# block_base_M.net
KiCad netlist of a schematic drawn in EAGLE
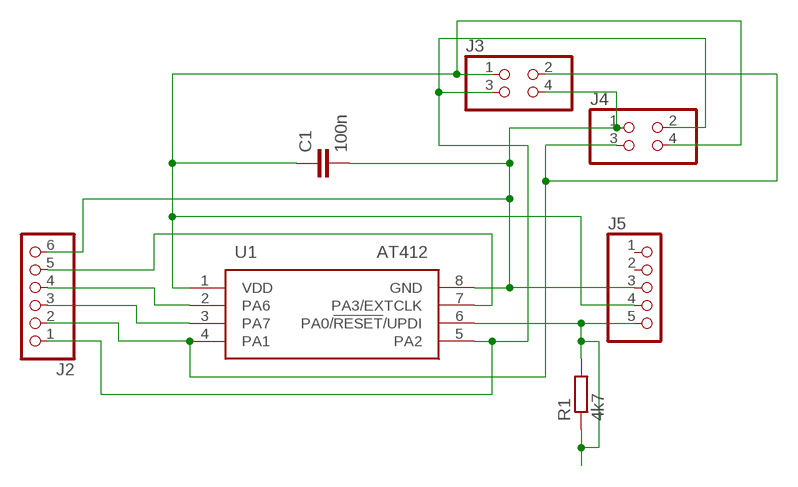
[diagram p0: schematic, sheet 1]

(export (version "E")
  (design (tool "Eeschema 10.0.6"))
  (components
    (comp (ref "C1")
      (value "100n")
      (footprint "eagle-import:C0603")
      (libsource (lib "eagle-import") (part "C-EUC0603"))
    )
    (comp (ref "J2")
      (value "PINHD-1X6")
      (footprint "eagle-import:1X06")
      (libsource (lib "eagle-import") (part "PINHD-1X6"))
    )
    (comp (ref "J3")
      (value "PINHD-2X2")
      (footprint "eagle-import:2X02")
      (libsource (lib "eagle-import") (part "PINHD-2X2"))
    )
    (comp (ref "J4")
      (value "PINHD-2X2")
      (footprint "eagle-import:2X02")
      (libsource (lib "eagle-import") (part "PINHD-2X2"))
    )
    (comp (ref "J5")
      (value "PINHD-1X5")
      (footprint "eagle-import:1X05")
      (libsource (lib "eagle-import") (part "PINHD-1X5"))
    )
    (comp (ref "R1")
      (value "4k7")
      (footprint "eagle-import:R0603")
      (libsource (lib "eagle-import") (part "R-EU_R0603"))
    )
    (comp (ref "U1")
      (value "AT412")
      (footprint "eagle-import:SOIC127P600X175-8N")
      (fields
        (field (name "MANUFACTURER_PART_NUMBER") "ATTINY412-SSN")
        (field (name "MOUSER_PART_NUMBER") "579-ATTINY412-SSN")
      )
      (libsource (lib "eagle-import") (part "ATTINY412-SSN"))
    )
  )
  (nets
    (net (code "1") (name "Net-(U1-GND)") (class "Default")
      (node (ref "C1") (pin "2") (pinfunction "2_2") (pintype "passive"))
      (node (ref "J2") (pin "6") (pinfunction "6_6") (pintype "passive"))
      (node (ref "J3") (pin "4") (pinfunction "4_4") (pintype "passive"))
      (node (ref "J4") (pin "1") (pinfunction "1_1") (pintype "passive"))
      (node (ref "J5") (pin "3") (pinfunction "3_3") (pintype "passive"))
      (node (ref "U1") (pin "8") (pinfunction "GND_8") (pintype "bidirectional"))
    )
    (net (code "2") (name "Net-(U1-PA0{slash}~{RESET}{slash}UPDI)") (class "Default")
      (node (ref "J5") (pin "5") (pinfunction "5_5") (pintype "passive"))
      (node (ref "R1") (pin "1") (pinfunction "1_1") (pintype "passive"))
      (node (ref "R1") (pin "2") (pinfunction "2_2") (pintype "passive"))
      (node (ref "U1") (pin "6") (pinfunction "PA0/~{RESET}/UPDI_6") (pintype "bidirectional"))
    )
    (net (code "3") (name "Net-(U1-PA1)") (class "Default")
      (node (ref "J2") (pin "2") (pinfunction "2_2") (pintype "passive"))
      (node (ref "J3") (pin "2") (pinfunction "2_2") (pintype "passive"))
      (node (ref "J4") (pin "3") (pinfunction "3_3") (pintype "passive"))
      (node (ref "U1") (pin "4") (pinfunction "PA1_4") (pintype "bidirectional"))
    )
    (net (code "4") (name "Net-(U1-PA2)") (class "Default")
      (node (ref "J2") (pin "1") (pinfunction "1_1") (pintype "passive"))
      (node (ref "J3") (pin "3") (pinfunction "3_3") (pintype "passive"))
      (node (ref "J4") (pin "2") (pinfunction "2_2") (pintype "passive"))
      (node (ref "U1") (pin "5") (pinfunction "PA2_5") (pintype "bidirectional"))
    )
    (net (code "5") (name "Net-(U1-PA3{slash}EXTCLK)") (class "Default")
      (node (ref "J2") (pin "5") (pinfunction "5_5") (pintype "passive"))
      (node (ref "U1") (pin "7") (pinfunction "PA3/EXTCLK_7") (pintype "bidirectional"))
    )
    (net (code "6") (name "Net-(U1-PA6)") (class "Default")
      (node (ref "J2") (pin "4") (pinfunction "4_4") (pintype "passive"))
      (node (ref "U1") (pin "2") (pinfunction "PA6_2") (pintype "bidirectional"))
    )
    (net (code "7") (name "Net-(U1-PA7)") (class "Default")
      (node (ref "J2") (pin "3") (pinfunction "3_3") (pintype "passive"))
      (node (ref "U1") (pin "3") (pinfunction "PA7_3") (pintype "bidirectional"))
    )
    (net (code "8") (name "Net-(U1-VDD)") (class "Default")
      (node (ref "C1") (pin "1") (pinfunction "1_1") (pintype "passive"))
      (node (ref "J3") (pin "1") (pinfunction "1_1") (pintype "passive"))
      (node (ref "J4") (pin "4") (pinfunction "4_4") (pintype "passive"))
      (node (ref "J5") (pin "4") (pinfunction "4_4") (pintype "passive"))
      (node (ref "U1") (pin "1") (pinfunction "VDD_1") (pintype "bidirectional"))
    )
    (net (code "9") (name "unconnected-(J5-Pad1)") (class "Default")
      (node (ref "J5") (pin "1") (pinfunction "1_1") (pintype "passive"))
    )
    (net (code "10") (name "unconnected-(J5-Pad2)") (class "Default")
      (node (ref "J5") (pin "2") (pinfunction "2_2") (pintype "passive"))
    )
  )
)
